# SD_Card.net
KiCad netlist of a schematic drawn in Altium Designer
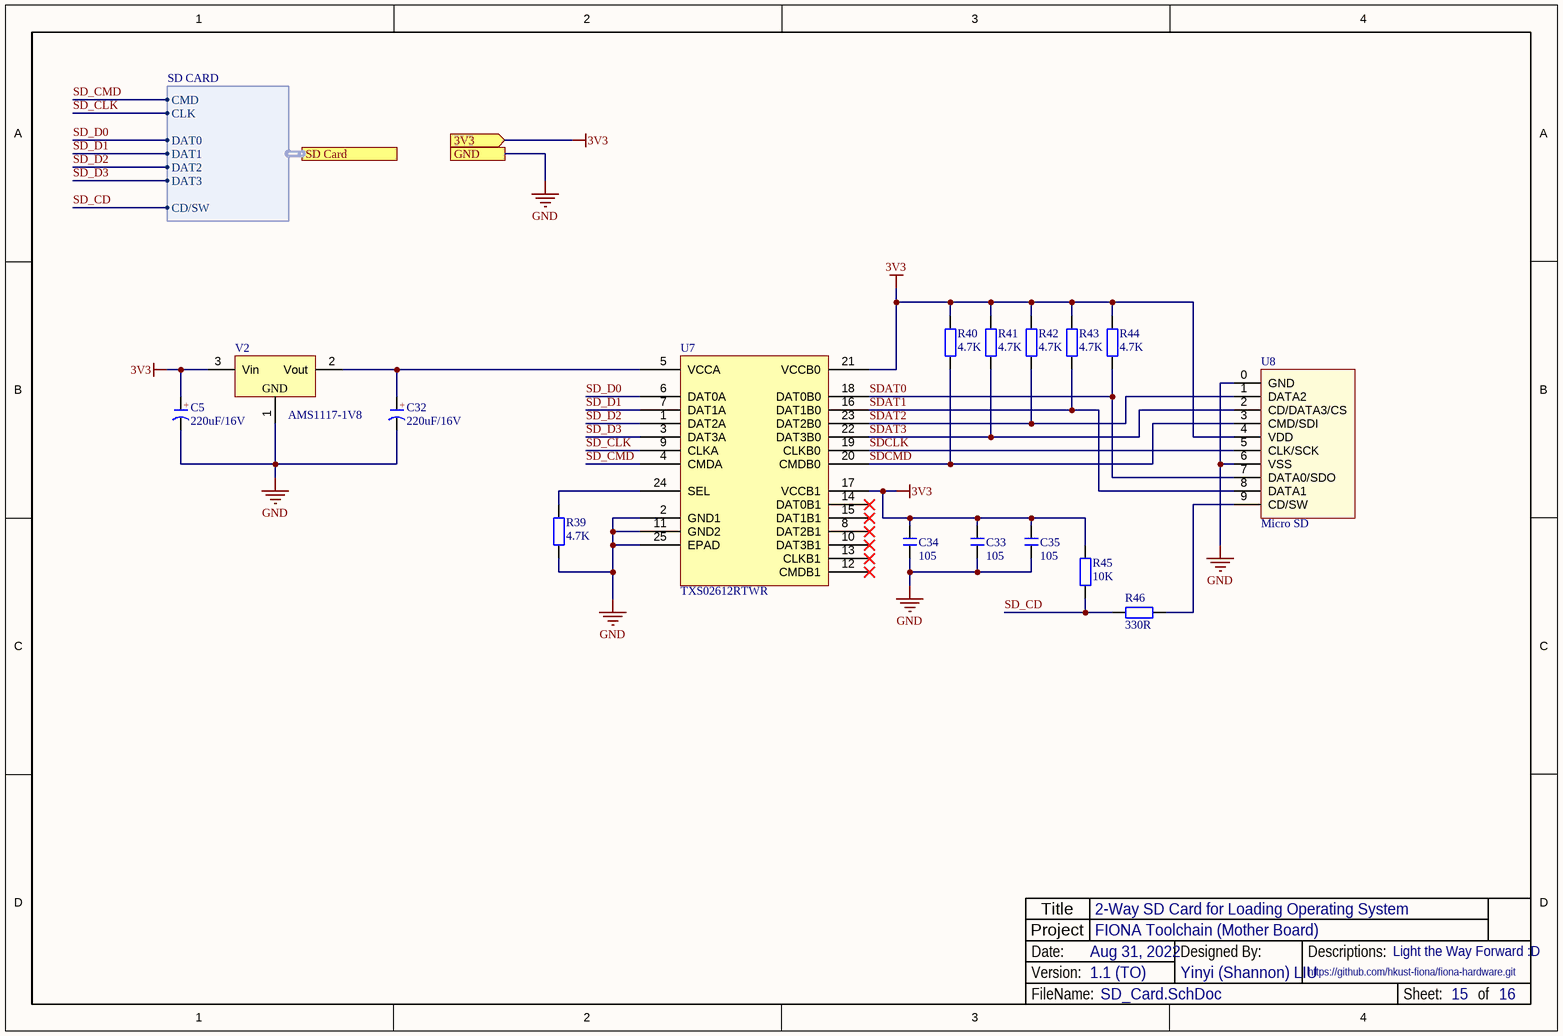
[diagram p0: SD_Card.SchDoc]

(export (version "E")
  (design (tool "Eeschema 10.0.6"))
  (components
    (comp (ref "C5")
      (value "220uF/16V")
      (footprint "CM D(6.3*7.7)")
      (description "贴片电解电容 C4054381")
      (fields (field (name "版权归属") "封装库来自淘宝 ID：黄晶宝石"))
      (libsource (lib "0.1 - 电阻-电容-电感") (part "CE_SMD"))
    )
    (comp (ref "C32")
      (value "220uF/16V")
      (footprint "CM D(6.3*7.7)")
      (description "贴片电解电容 C4054381")
      (fields (field (name "版权归属") "封装库来自淘宝 ID：黄晶宝石"))
      (libsource (lib "0.1 - 电阻-电容-电感") (part "CE_SMD"))
    )
    (comp (ref "C33")
      (value "105")
      (footprint "C 0603_L")
      (description "贴片电容")
      (libsource (lib "0.1 - 电阻-电容-电感") (part "C"))
    )
    (comp (ref "C34")
      (value "105")
      (footprint "C 0603_L")
      (description "贴片电容")
      (libsource (lib "0.1 - 电阻-电容-电感") (part "C"))
    )
    (comp (ref "C35")
      (value "105")
      (footprint "C 0603_L")
      (description "贴片电容")
      (libsource (lib "0.1 - 电阻-电容-电感") (part "C"))
    )
    (comp (ref "R39")
      (value "4.7K")
      (footprint "R 0201_L")
      (description "贴片电阻")
      (fields (field (name "版权归属") "来自淘宝 ID：黄晶宝石"))
      (libsource (lib "0.1 - 电阻-电容-电感") (part "R"))
    )
    (comp (ref "R40")
      (value "4.7K")
      (footprint "R 0201_L")
      (description "贴片电阻")
      (fields (field (name "版权归属") "来自淘宝 ID：黄晶宝石"))
      (libsource (lib "0.1 - 电阻-电容-电感") (part "R"))
    )
    (comp (ref "R41")
      (value "4.7K")
      (footprint "R 0201_L")
      (description "贴片电阻")
      (fields (field (name "版权归属") "来自淘宝 ID：黄晶宝石"))
      (libsource (lib "0.1 - 电阻-电容-电感") (part "R"))
    )
    (comp (ref "R42")
      (value "4.7K")
      (footprint "R 0201_L")
      (description "贴片电阻")
      (fields (field (name "版权归属") "来自淘宝 ID：黄晶宝石"))
      (libsource (lib "0.1 - 电阻-电容-电感") (part "R"))
    )
    (comp (ref "R43")
      (value "4.7K")
      (footprint "R 0201_L")
      (description "贴片电阻")
      (fields (field (name "版权归属") "来自淘宝 ID：黄晶宝石"))
      (libsource (lib "0.1 - 电阻-电容-电感") (part "R"))
    )
    (comp (ref "R44")
      (value "4.7K")
      (footprint "R 0201_L")
      (description "贴片电阻")
      (fields (field (name "版权归属") "来自淘宝 ID：黄晶宝石"))
      (libsource (lib "0.1 - 电阻-电容-电感") (part "R"))
    )
    (comp (ref "R45")
      (value "10K")
      (footprint "R 0201_L")
      (description "贴片电阻")
      (fields (field (name "版权归属") "来自淘宝 ID：黄晶宝石"))
      (libsource (lib "0.1 - 电阻-电容-电感") (part "R"))
    )
    (comp (ref "R46")
      (value "330R")
      (footprint "R 0201_L")
      (description "贴片电阻")
      (fields (field (name "版权归属") "来自淘宝 ID：黄晶宝石"))
      (libsource (lib "0.1 - 电阻-电容-电感") (part "R"))
    )
    (comp (ref "U7")
      (value "TXS02612RTWR")
      (footprint "QFN24_RTW")
      (libsource (lib "领航者ZYNQ底板SCH&PCB封装库") (part "TXS02612RTWR"))
    )
    (comp (ref "U8")
      (value "Micro SD")
      (footprint "Micro SD")
      (description "Micro SD卡")
      (fields (field (name "版权归属") "源创客"))
      (libsource (lib "领航者ZYNQ底板SCH&PCB封装库") (part "Micro SD"))
    )
    (comp (ref "V2")
      (value "AMS1117-1V8")
      (footprint "SOT223_L")
      (description "三端稳压芯片")
      (libsource (lib "1.1 - 电源类芯片") (part "AMS1117"))
    )
  )
  (nets
    (net (code "3") (name "/SDAT0") (class "Default")
      (node (ref "R44") (pin "1") (pinfunction "1_1") (pintype "passive"))
      (node (ref "U7") (pin "18") (pinfunction "DAT0B0_18") (pintype "passive"))
      (node (ref "U8") (pin "7") (pinfunction "DATA0/SDO_7") (pintype "passive"))
    )
    (net (code "4") (name "/SDAT1") (class "Default")
      (node (ref "R43") (pin "1") (pinfunction "1_1") (pintype "passive"))
      (node (ref "U7") (pin "16") (pinfunction "DAT1B0_16") (pintype "passive"))
      (node (ref "U8") (pin "8") (pinfunction "DATA1_8") (pintype "passive"))
    )
    (net (code "5") (name "/SDAT2") (class "Default")
      (node (ref "R42") (pin "1") (pinfunction "1_1") (pintype "passive"))
      (node (ref "U7") (pin "23") (pinfunction "DAT2B0_23") (pintype "passive"))
      (node (ref "U8") (pin "1") (pinfunction "DATA2_1") (pintype "passive"))
    )
    (net (code "6") (name "/SDAT3") (class "Default")
      (node (ref "R41") (pin "1") (pinfunction "1_1") (pintype "passive"))
      (node (ref "U7") (pin "22") (pinfunction "DAT3B0_22") (pintype "passive"))
      (node (ref "U8") (pin "2") (pinfunction "CD/DATA3/CS_2") (pintype "passive"))
    )
    (net (code "7") (name "/SDCLK") (class "Default")
      (node (ref "U7") (pin "19") (pinfunction "CLKB0_19") (pintype "passive"))
      (node (ref "U8") (pin "5") (pinfunction "CLK/SCK_5") (pintype "passive"))
    )
    (net (code "8") (name "/SDCMD") (class "Default")
      (node (ref "R40") (pin "1") (pinfunction "1_1") (pintype "passive"))
      (node (ref "U7") (pin "20") (pinfunction "CMDB0_20") (pintype "passive"))
      (node (ref "U8") (pin "3") (pinfunction "CMD/SDI_3") (pintype "passive"))
    )
    (net (code "9") (name "/SD_CD") (class "Default")
      (node (ref "R45") (pin "1") (pinfunction "1_1") (pintype "passive"))
      (node (ref "R46") (pin "2") (pinfunction "2_2") (pintype "passive"))
    )
    (net (code "10") (name "/SD_CLK") (class "Default")
      (node (ref "U7") (pin "9") (pinfunction "CLKA_9") (pintype "passive"))
    )
    (net (code "11") (name "/SD_CMD") (class "Default")
      (node (ref "U7") (pin "4") (pinfunction "CMDA_4") (pintype "passive"))
    )
    (net (code "12") (name "/SD_D0") (class "Default")
      (node (ref "U7") (pin "6") (pinfunction "DAT0A_6") (pintype "passive"))
    )
    (net (code "13") (name "/SD_D1") (class "Default")
      (node (ref "U7") (pin "7") (pinfunction "DAT1A_7") (pintype "passive"))
    )
    (net (code "14") (name "/SD_D2") (class "Default")
      (node (ref "U7") (pin "1") (pinfunction "DAT2A_1") (pintype "passive"))
    )
    (net (code "15") (name "/SD_D3") (class "Default")
      (node (ref "U7") (pin "3") (pinfunction "DAT3A_3") (pintype "passive"))
    )
    (net (code "17") (name "3V3") (class "Default")
      (node (ref "C33") (pin "2") (pinfunction "2_2") (pintype "passive"))
      (node (ref "C34") (pin "2") (pinfunction "2_2") (pintype "passive"))
      (node (ref "C35") (pin "2") (pinfunction "2_2") (pintype "passive"))
      (node (ref "C5") (pin "1") (pinfunction "A_1") (pintype "passive"))
      (node (ref "R40") (pin "2") (pinfunction "2_2") (pintype "passive"))
      (node (ref "R41") (pin "2") (pinfunction "2_2") (pintype "passive"))
      (node (ref "R42") (pin "2") (pinfunction "2_2") (pintype "passive"))
      (node (ref "R43") (pin "2") (pinfunction "2_2") (pintype "passive"))
      (node (ref "R44") (pin "2") (pinfunction "2_2") (pintype "passive"))
      (node (ref "R45") (pin "2") (pinfunction "2_2") (pintype "passive"))
      (node (ref "U7") (pin "17") (pinfunction "VCCB1_17") (pintype "passive"))
      (node (ref "U7") (pin "21") (pinfunction "VCCB0_21") (pintype "passive"))
      (node (ref "U8") (pin "4") (pinfunction "VDD_4") (pintype "passive"))
      (node (ref "V2") (pin "3") (pinfunction "Vin_3") (pintype "passive"))
    )
    (net (code "18") (name "GND") (class "Default")
      (node (ref "C32") (pin "2") (pinfunction "K_2") (pintype "passive"))
      (node (ref "C33") (pin "1") (pinfunction "1_1") (pintype "passive"))
      (node (ref "C34") (pin "1") (pinfunction "1_1") (pintype "passive"))
      (node (ref "C35") (pin "1") (pinfunction "1_1") (pintype "passive"))
      (node (ref "C5") (pin "2") (pinfunction "K_2") (pintype "passive"))
      (node (ref "R39") (pin "1") (pinfunction "1_1") (pintype "passive"))
      (node (ref "U7") (pin "11") (pinfunction "GND2_11") (pintype "passive"))
      (node (ref "U7") (pin "2") (pinfunction "GND1_2") (pintype "passive"))
      (node (ref "U7") (pin "25") (pinfunction "EPAD_25") (pintype "passive"))
      (node (ref "U8") (pin "0") (pinfunction "GND_0") (pintype "passive"))
      (node (ref "U8") (pin "6") (pinfunction "VSS_6") (pintype "passive"))
      (node (ref "V2") (pin "1") (pinfunction "GND_1") (pintype "passive"))
    )
    (net (code "19") (name "Net-(C32-A)") (class "Default")
      (node (ref "C32") (pin "1") (pinfunction "A_1") (pintype "passive"))
      (node (ref "U7") (pin "5") (pinfunction "VCCA_5") (pintype "passive"))
      (node (ref "V2") (pin "2") (pinfunction "Vout_2") (pintype "passive"))
    )
    (net (code "20") (name "Net-(U7-SEL)") (class "Default")
      (node (ref "R39") (pin "2") (pinfunction "2_2") (pintype "passive"))
      (node (ref "U7") (pin "24") (pinfunction "SEL_24") (pintype "passive"))
    )
    (net (code "21") (name "Net-(U8-CD{slash}SW)") (class "Default")
      (node (ref "R46") (pin "1") (pinfunction "1_1") (pintype "passive"))
      (node (ref "U8") (pin "9") (pinfunction "CD/SW_9") (pintype "passive"))
    )
    (net (code "22") (name "unconnected-(U7-CLKB1-Pad13)") (class "Default")
      (node (ref "U7") (pin "13") (pinfunction "CLKB1_13") (pintype "passive+no_connect"))
    )
    (net (code "23") (name "unconnected-(U7-CMDB1-Pad12)") (class "Default")
      (node (ref "U7") (pin "12") (pinfunction "CMDB1_12") (pintype "passive+no_connect"))
    )
    (net (code "24") (name "unconnected-(U7-DAT0B1-Pad14)") (class "Default")
      (node (ref "U7") (pin "14") (pinfunction "DAT0B1_14") (pintype "passive+no_connect"))
    )
    (net (code "25") (name "unconnected-(U7-DAT1B1-Pad15)") (class "Default")
      (node (ref "U7") (pin "15") (pinfunction "DAT1B1_15") (pintype "passive+no_connect"))
    )
    (net (code "26") (name "unconnected-(U7-DAT2B1-Pad8)") (class "Default")
      (node (ref "U7") (pin "8") (pinfunction "DAT2B1_8") (pintype "passive+no_connect"))
    )
    (net (code "27") (name "unconnected-(U7-DAT3B1-Pad10)") (class "Default")
      (node (ref "U7") (pin "10") (pinfunction "DAT3B1_10") (pintype "passive+no_connect"))
    )
  )
)
